# SOT23-8-normal.net
KiCad netlist of a schematic drawn in EAGLE
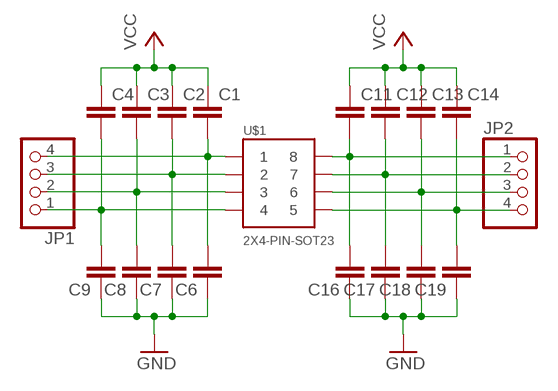
[diagram p0: schematic, sheet 1]

(export (version "E")
  (design (tool "Eeschema 10.0.6"))
  (components
    (comp (ref "C1")
      (value "C-EUC0603")
      (footprint "eagle-import:C0603")
      (libsource (lib "eagle-import") (part "C-EUC0603"))
    )
    (comp (ref "C2")
      (value "C-EUC0603")
      (footprint "eagle-import:C0603")
      (libsource (lib "eagle-import") (part "C-EUC0603"))
    )
    (comp (ref "C3")
      (value "C-EUC0603")
      (footprint "eagle-import:C0603")
      (libsource (lib "eagle-import") (part "C-EUC0603"))
    )
    (comp (ref "C4")
      (value "C-EUC0603")
      (footprint "eagle-import:C0603")
      (libsource (lib "eagle-import") (part "C-EUC0603"))
    )
    (comp (ref "C6")
      (value "C-EUC0805")
      (footprint "eagle-import:C0805")
      (libsource (lib "eagle-import") (part "C-EUC0805"))
    )
    (comp (ref "C7")
      (value "C-EUC0805")
      (footprint "eagle-import:C0805")
      (libsource (lib "eagle-import") (part "C-EUC0805"))
    )
    (comp (ref "C8")
      (value "C-EUC0805")
      (footprint "eagle-import:C0805")
      (libsource (lib "eagle-import") (part "C-EUC0805"))
    )
    (comp (ref "C9")
      (value "C-EUC0805")
      (footprint "eagle-import:C0805")
      (libsource (lib "eagle-import") (part "C-EUC0805"))
    )
    (comp (ref "C11")
      (value "C-EUC0603")
      (footprint "eagle-import:C0603")
      (libsource (lib "eagle-import") (part "C-EUC0603"))
    )
    (comp (ref "C12")
      (value "C-EUC0603")
      (footprint "eagle-import:C0603")
      (libsource (lib "eagle-import") (part "C-EUC0603"))
    )
    (comp (ref "C13")
      (value "C-EUC0603")
      (footprint "eagle-import:C0603")
      (libsource (lib "eagle-import") (part "C-EUC0603"))
    )
    (comp (ref "C14")
      (value "C-EUC0603")
      (footprint "eagle-import:C0603")
      (libsource (lib "eagle-import") (part "C-EUC0603"))
    )
    (comp (ref "C16")
      (value "C-EUC0805")
      (footprint "eagle-import:C0805")
      (libsource (lib "eagle-import") (part "C-EUC0805"))
    )
    (comp (ref "C17")
      (value "C-EUC0805")
      (footprint "eagle-import:C0805")
      (libsource (lib "eagle-import") (part "C-EUC0805"))
    )
    (comp (ref "C18")
      (value "C-EUC0805")
      (footprint "eagle-import:C0805")
      (libsource (lib "eagle-import") (part "C-EUC0805"))
    )
    (comp (ref "C19")
      (value "C-EUC0805")
      (footprint "eagle-import:C0805")
      (libsource (lib "eagle-import") (part "C-EUC0805"))
    )
    (comp (ref "JP1")
      (value "PINHD-1X4")
      (footprint "eagle-import:1X04")
      (libsource (lib "eagle-import") (part "PINHD-1X4"))
    )
    (comp (ref "JP2")
      (value "PINHD-1X4")
      (footprint "eagle-import:1X04")
      (libsource (lib "eagle-import") (part "PINHD-1X4"))
    )
    (comp (ref "U$1")
      (value "2X4-PIN-SOT23")
      (footprint "eagle-import:SOT23-8")
      (libsource (lib "eagle-import") (part "2X4-PIN-SOT23"))
    )
  )
  (nets
    (net (code "1") (name "GND") (class "Default")
      (node (ref "C16") (pin "1") (pinfunction "1_1") (pintype "passive"))
      (node (ref "C17") (pin "1") (pinfunction "1_1") (pintype "passive"))
      (node (ref "C18") (pin "1") (pinfunction "1_1") (pintype "passive"))
      (node (ref "C19") (pin "1") (pinfunction "1_1") (pintype "passive"))
      (node (ref "C6") (pin "1") (pinfunction "1_1") (pintype "passive"))
      (node (ref "C7") (pin "1") (pinfunction "1_1") (pintype "passive"))
      (node (ref "C8") (pin "1") (pinfunction "1_1") (pintype "passive"))
      (node (ref "C9") (pin "1") (pinfunction "1_1") (pintype "passive"))
    )
    (net (code "2") (name "Net-(U$1-1)") (class "Default")
      (node (ref "C1") (pin "2") (pinfunction "2_2") (pintype "passive"))
      (node (ref "C6") (pin "2") (pinfunction "2_2") (pintype "passive"))
      (node (ref "JP1") (pin "4") (pinfunction "4_4") (pintype "passive"))
      (node (ref "U$1") (pin "P$1") (pinfunction "1_P$1") (pintype "bidirectional"))
    )
    (net (code "3") (name "Net-(U$1-2)") (class "Default")
      (node (ref "C2") (pin "2") (pinfunction "2_2") (pintype "passive"))
      (node (ref "C7") (pin "2") (pinfunction "2_2") (pintype "passive"))
      (node (ref "JP1") (pin "3") (pinfunction "3_3") (pintype "passive"))
      (node (ref "U$1") (pin "P$2") (pinfunction "2_P$2") (pintype "bidirectional"))
    )
    (net (code "4") (name "Net-(U$1-3)") (class "Default")
      (node (ref "C3") (pin "2") (pinfunction "2_2") (pintype "passive"))
      (node (ref "C8") (pin "2") (pinfunction "2_2") (pintype "passive"))
      (node (ref "JP1") (pin "2") (pinfunction "2_2") (pintype "passive"))
      (node (ref "U$1") (pin "P$3") (pinfunction "3_P$3") (pintype "bidirectional"))
    )
    (net (code "5") (name "Net-(U$1-4)") (class "Default")
      (node (ref "C4") (pin "2") (pinfunction "2_2") (pintype "passive"))
      (node (ref "C9") (pin "2") (pinfunction "2_2") (pintype "passive"))
      (node (ref "JP1") (pin "1") (pinfunction "1_1") (pintype "passive"))
      (node (ref "U$1") (pin "P$4") (pinfunction "4_P$4") (pintype "bidirectional"))
    )
    (net (code "6") (name "Net-(U$1-5)") (class "Default")
      (node (ref "C14") (pin "2") (pinfunction "2_2") (pintype "passive"))
      (node (ref "C19") (pin "2") (pinfunction "2_2") (pintype "passive"))
      (node (ref "JP2") (pin "4") (pinfunction "4_4") (pintype "passive"))
      (node (ref "U$1") (pin "P$5") (pinfunction "5_P$5") (pintype "bidirectional"))
    )
    (net (code "7") (name "Net-(U$1-6)") (class "Default")
      (node (ref "C13") (pin "2") (pinfunction "2_2") (pintype "passive"))
      (node (ref "C18") (pin "2") (pinfunction "2_2") (pintype "passive"))
      (node (ref "JP2") (pin "3") (pinfunction "3_3") (pintype "passive"))
      (node (ref "U$1") (pin "P$6") (pinfunction "6_P$6") (pintype "bidirectional"))
    )
    (net (code "8") (name "Net-(U$1-7)") (class "Default")
      (node (ref "C12") (pin "2") (pinfunction "2_2") (pintype "passive"))
      (node (ref "C17") (pin "2") (pinfunction "2_2") (pintype "passive"))
      (node (ref "JP2") (pin "2") (pinfunction "2_2") (pintype "passive"))
      (node (ref "U$1") (pin "P$7") (pinfunction "7_P$7") (pintype "bidirectional"))
    )
    (net (code "9") (name "Net-(U$1-8)") (class "Default")
      (node (ref "C11") (pin "2") (pinfunction "2_2") (pintype "passive"))
      (node (ref "C16") (pin "2") (pinfunction "2_2") (pintype "passive"))
      (node (ref "JP2") (pin "1") (pinfunction "1_1") (pintype "passive"))
      (node (ref "U$1") (pin "P$8") (pinfunction "8_P$8") (pintype "bidirectional"))
    )
    (net (code "10") (name "VCC") (class "Default")
      (node (ref "C1") (pin "1") (pinfunction "1_1") (pintype "passive"))
      (node (ref "C11") (pin "1") (pinfunction "1_1") (pintype "passive"))
      (node (ref "C12") (pin "1") (pinfunction "1_1") (pintype "passive"))
      (node (ref "C13") (pin "1") (pinfunction "1_1") (pintype "passive"))
      (node (ref "C14") (pin "1") (pinfunction "1_1") (pintype "passive"))
      (node (ref "C2") (pin "1") (pinfunction "1_1") (pintype "passive"))
      (node (ref "C3") (pin "1") (pinfunction "1_1") (pintype "passive"))
      (node (ref "C4") (pin "1") (pinfunction "1_1") (pintype "passive"))
    )
  )
)
